# neurite-core.net
KiCad netlist of a schematic drawn in EAGLE
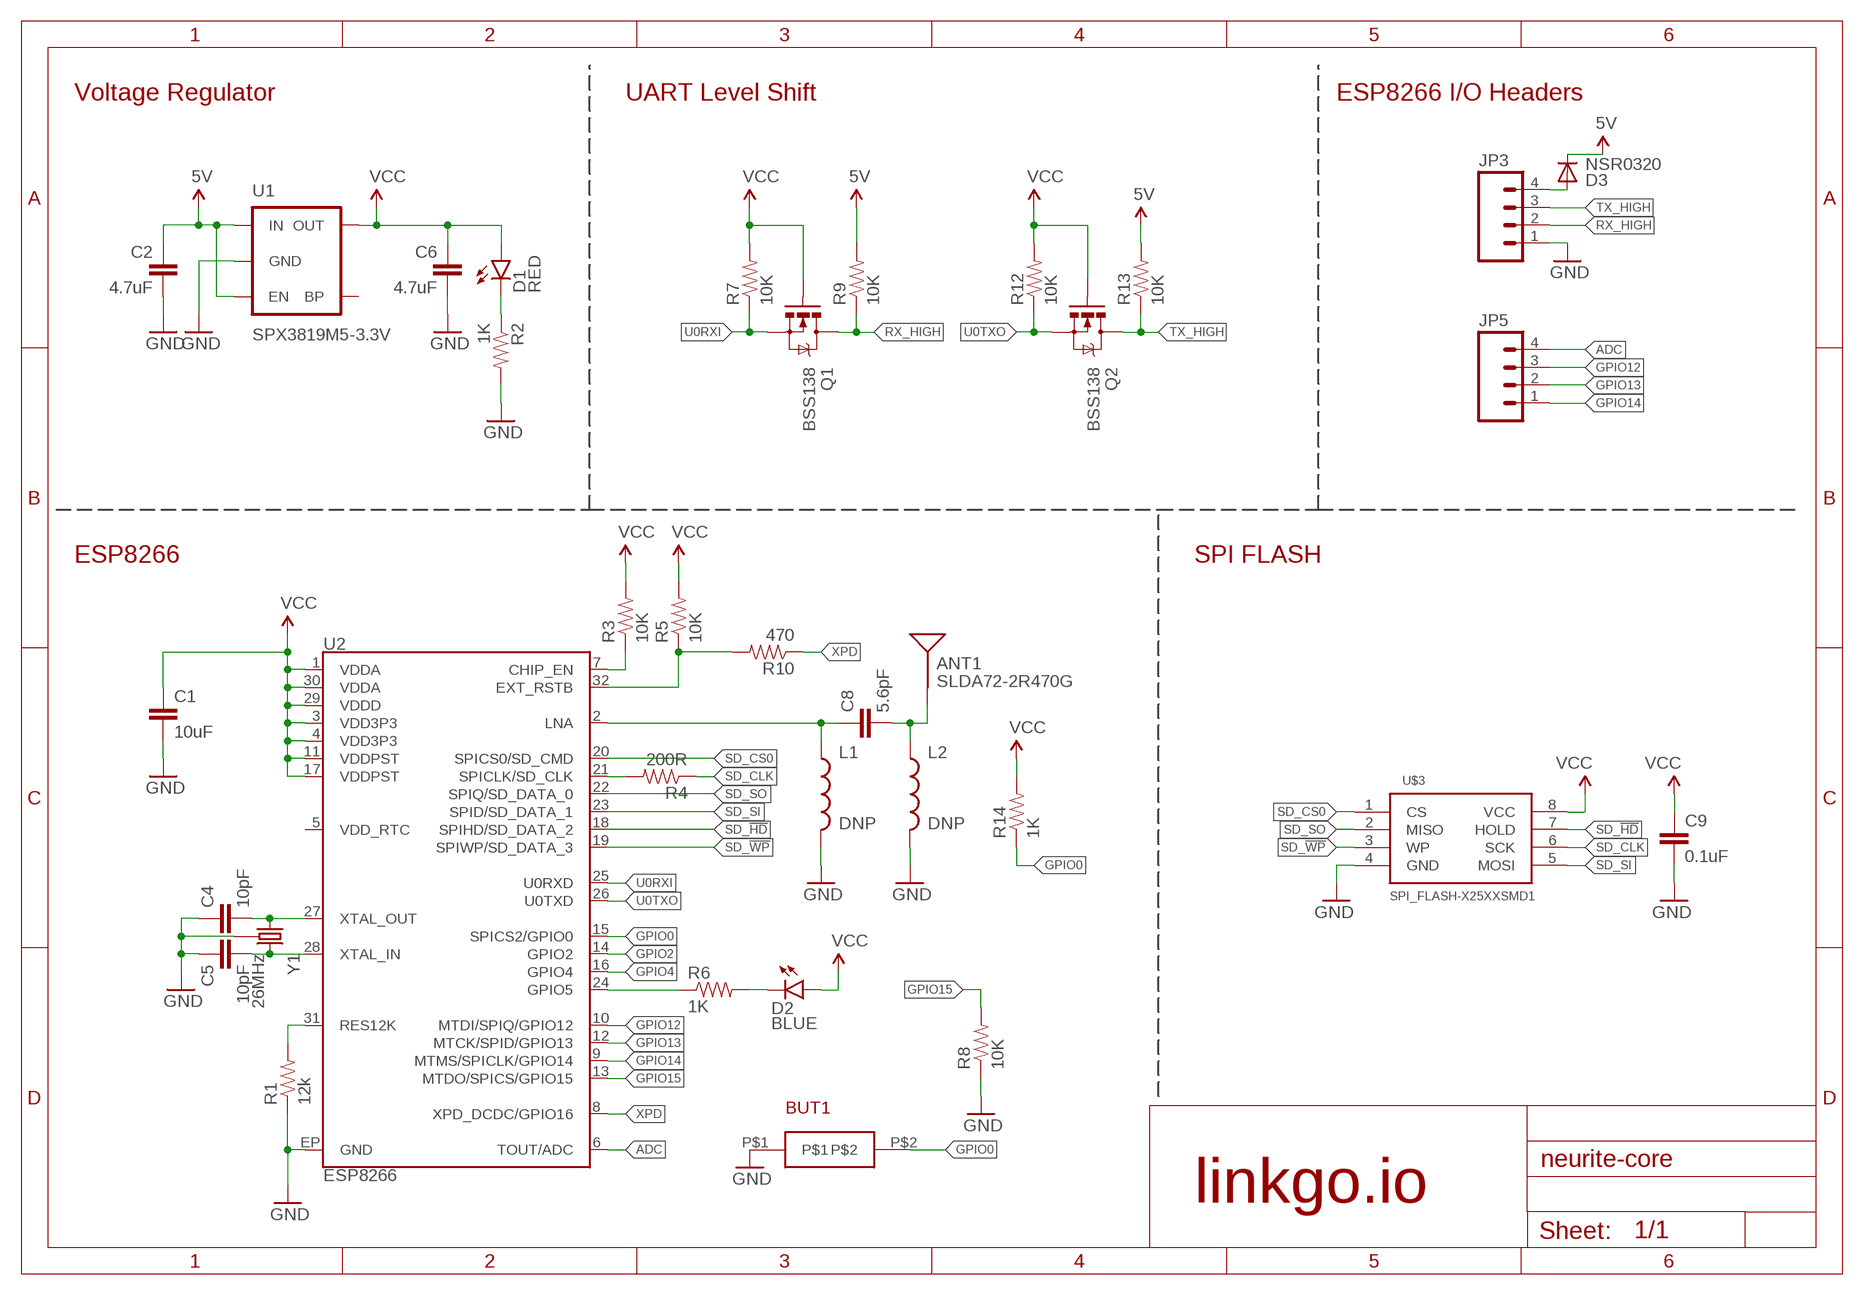
[diagram p0: schematic, sheet 1]

(export (version "E")
  (design (tool "Eeschema 10.0.6"))
  (components
    (comp (ref "ANT1")
      (value "SLDA72-2R470G")
      (footprint "eagle-import:ANTENNA-CHIP6")
      (libsource (lib "eagle-import") (part "ANTENNA2SMD6"))
    )
    (comp (ref "BUT1")
      (value "SWITCH")
      (footprint "eagle-import:SWITCH")
      (libsource (lib "eagle-import") (part "SWITCH"))
    )
    (comp (ref "C1")
      (value "10uF")
      (footprint "eagle-import:0402-CAP")
      (libsource (lib "eagle-import") (part "CAP0402-CAP"))
    )
    (comp (ref "C2")
      (value "4.7uF")
      (footprint "eagle-import:0805")
      (libsource (lib "eagle-import") (part "1.0UF-25V-+80/-20(0805)"))
    )
    (comp (ref "C4")
      (value "10pF")
      (footprint "eagle-import:0402-CAP")
      (libsource (lib "eagle-import") (part "CAP0402-CAP"))
    )
    (comp (ref "C5")
      (value "10pF")
      (footprint "eagle-import:0402-CAP")
      (libsource (lib "eagle-import") (part "CAP0402-CAP"))
    )
    (comp (ref "C6")
      (value "4.7uF")
      (footprint "eagle-import:0603-CAP")
      (libsource (lib "eagle-import") (part "2.2UF-10V-20%(0603)"))
    )
    (comp (ref "C8")
      (value "5.6pF")
      (footprint "eagle-import:0402-CAP")
      (libsource (lib "eagle-import") (part "CAP0402-CAP"))
    )
    (comp (ref "C9")
      (value "0.1uF")
      (footprint "eagle-import:0402-CAP")
      (libsource (lib "eagle-import") (part "CAP0402-CAP"))
    )
    (comp (ref "D1")
      (value "RED")
      (footprint "eagle-import:LED-0603")
      (libsource (lib "eagle-import") (part "LED-RED0603"))
    )
    (comp (ref "D2")
      (value "BLUE")
      (footprint "eagle-import:LED-0603")
      (libsource (lib "eagle-import") (part "LED-BLUE0603"))
    )
    (comp (ref "D3")
      (value "NSR0320")
      (footprint "eagle-import:SOD-323")
      (libsource (lib "eagle-import") (part "DIODESOD"))
    )
    (comp (ref "JP3")
      (value "M04PTH")
      (footprint "eagle-import:1X04")
      (libsource (lib "eagle-import") (part "M04PTH"))
    )
    (comp (ref "JP5")
      (value "M04PTH")
      (footprint "eagle-import:1X04")
      (libsource (lib "eagle-import") (part "M04PTH"))
    )
    (comp (ref "L1")
      (value "DNP")
      (footprint "eagle-import:C0402")
      (libsource (lib "eagle-import") (part "INDUCTOR0402"))
    )
    (comp (ref "L2")
      (value "DNP")
      (footprint "eagle-import:C0402")
      (libsource (lib "eagle-import") (part "INDUCTOR0402"))
    )
    (comp (ref "Q1")
      (value "BSS138")
      (footprint "eagle-import:SOT23-3")
      (libsource (lib "eagle-import") (part "MOSFET-NCHANNELBSS138"))
    )
    (comp (ref "Q2")
      (value "BSS138")
      (footprint "eagle-import:SOT23-3")
      (libsource (lib "eagle-import") (part "MOSFET-NCHANNELBSS138"))
    )
    (comp (ref "R1")
      (value "12k")
      (footprint "eagle-import:0402-RES")
      (libsource (lib "eagle-import") (part "RESISTOR0402-RES"))
    )
    (comp (ref "R2")
      (value "1K")
      (footprint "eagle-import:0402-RES")
      (libsource (lib "eagle-import") (part "RESISTOR0402-RES"))
    )
    (comp (ref "R3")
      (value "10K")
      (footprint "eagle-import:0402-RES")
      (libsource (lib "eagle-import") (part "RESISTOR0402-RES"))
    )
    (comp (ref "R4")
      (value "200R")
      (footprint "eagle-import:0402-RES")
      (libsource (lib "eagle-import") (part "RESISTOR0402-RES"))
    )
    (comp (ref "R5")
      (value "10K")
      (footprint "eagle-import:0402-RES")
      (libsource (lib "eagle-import") (part "RESISTOR0402-RES"))
    )
    (comp (ref "R6")
      (value "1K")
      (footprint "eagle-import:0402-RES")
      (libsource (lib "eagle-import") (part "RESISTOR0402-RES"))
    )
    (comp (ref "R7")
      (value "10K")
      (footprint "eagle-import:0402-RES")
      (libsource (lib "eagle-import") (part "RESISTOR0402-RES"))
    )
    (comp (ref "R8")
      (value "10K")
      (footprint "eagle-import:0402-RES")
      (libsource (lib "eagle-import") (part "RESISTOR0402-RES"))
    )
    (comp (ref "R9")
      (value "10K")
      (footprint "eagle-import:0402-RES")
      (libsource (lib "eagle-import") (part "RESISTOR0402-RES"))
    )
    (comp (ref "R10")
      (value "470")
      (footprint "eagle-import:0402-RES")
      (libsource (lib "eagle-import") (part "RESISTOR0402-RES"))
    )
    (comp (ref "R12")
      (value "10K")
      (footprint "eagle-import:0402-RES")
      (libsource (lib "eagle-import") (part "RESISTOR0402-RES"))
    )
    (comp (ref "R13")
      (value "10K")
      (footprint "eagle-import:0402-RES")
      (libsource (lib "eagle-import") (part "RESISTOR0402-RES"))
    )
    (comp (ref "R14")
      (value "1K")
      (footprint "eagle-import:0402-RES")
      (libsource (lib "eagle-import") (part "RESISTOR0402-RES"))
    )
    (comp (ref "U$3")
      (value "SPI_FLASH-X25XXSMD1")
      (footprint "eagle-import:SO08-EIAJ")
      (libsource (lib "eagle-import") (part "SPI_FLASH-X25XXSMD1"))
    )
    (comp (ref "U1")
      (value "SPX3819M5-3.3V")
      (footprint "eagle-import:SOT23-5")
      (libsource (lib "eagle-import") (part "V_REG_LDOSMD"))
    )
    (comp (ref "U2")
      (value "ESP8266")
      (footprint "eagle-import:QFN32")
      (libsource (lib "eagle-import") (part "ESP8266"))
    )
    (comp (ref "Y1")
      (value "26MHz")
      (footprint "eagle-import:CRYSTAL-SMD-3.2X2.5")
      (libsource (lib "eagle-import") (part "CRYSTAL-GROUNDED3.2X2.5"))
    )
  )
  (nets
    (net (code "1") (name "/SD_~{HD}") (class "Default")
      (node (ref "U$3") (pin "7") (pinfunction "HOLD_7") (pintype "bidirectional"))
      (node (ref "U2") (pin "18") (pinfunction "SPIHD/SD_DATA_2_18") (pintype "bidirectional"))
    )
    (net (code "2") (name "/SD_~{WP}") (class "Default")
      (node (ref "U$3") (pin "3") (pinfunction "WP_3") (pintype "bidirectional"))
      (node (ref "U2") (pin "19") (pinfunction "SPIWP/SD_DATA_3_19") (pintype "bidirectional"))
    )
    (net (code "3") (name "5V") (class "Default")
      (node (ref "C2") (pin "1") (pinfunction "1_1") (pintype "passive"))
      (node (ref "D3") (pin "1") (pinfunction "C_1") (pintype "passive"))
      (node (ref "R13") (pin "2") (pinfunction "2_2") (pintype "passive"))
      (node (ref "R9") (pin "2") (pinfunction "2_2") (pintype "passive"))
      (node (ref "U1") (pin "1") (pinfunction "IN_1") (pintype "input"))
      (node (ref "U1") (pin "3") (pinfunction "EN_3") (pintype "input"))
    )
    (net (code "4") (name "ADC") (class "Default")
      (node (ref "JP5") (pin "4") (pinfunction "4_4") (pintype "passive"))
      (node (ref "U2") (pin "6") (pinfunction "TOUT/ADC_6") (pintype "bidirectional"))
    )
    (net (code "5") (name "GND") (class "Default")
      (node (ref "BUT1") (pin "P$1") (pinfunction "P$1_P$1") (pintype "bidirectional"))
      (node (ref "C1") (pin "2") (pinfunction "2_2") (pintype "passive"))
      (node (ref "C2") (pin "2") (pinfunction "2_2") (pintype "passive"))
      (node (ref "C4") (pin "1") (pinfunction "1_1") (pintype "passive"))
      (node (ref "C5") (pin "1") (pinfunction "1_1") (pintype "passive"))
      (node (ref "C6") (pin "2") (pinfunction "2_2") (pintype "passive"))
      (node (ref "C9") (pin "2") (pinfunction "2_2") (pintype "passive"))
      (node (ref "JP3") (pin "1") (pinfunction "1_1") (pintype "passive"))
      (node (ref "L1") (pin "2") (pinfunction "2_2") (pintype "passive"))
      (node (ref "L2") (pin "2") (pinfunction "2_2") (pintype "passive"))
      (node (ref "R1") (pin "1") (pinfunction "1_1") (pintype "passive"))
      (node (ref "R2") (pin "2") (pinfunction "2_2") (pintype "passive"))
      (node (ref "R8") (pin "1") (pinfunction "1_1") (pintype "passive"))
      (node (ref "U$3") (pin "4") (pinfunction "GND_4") (pintype "bidirectional"))
      (node (ref "U1") (pin "2") (pinfunction "GND_2") (pintype "input"))
      (node (ref "U2") (pin "EP") (pinfunction "GND_EP") (pintype "bidirectional"))
      (node (ref "Y1") (pin "2") (pinfunction "GND_2") (pintype "passive"))
      (node (ref "Y1") (pin "4") (pinfunction "GND_4") (pintype "passive"))
    )
    (net (code "6") (name "GPIO0") (class "Default")
      (node (ref "BUT1") (pin "P$2") (pinfunction "P$2_P$2") (pintype "bidirectional"))
      (node (ref "R14") (pin "1") (pinfunction "1_1") (pintype "passive"))
      (node (ref "U2") (pin "15") (pinfunction "SPICS2/GPIO0_15") (pintype "bidirectional"))
    )
    (net (code "7") (name "GPIO2") (class "Default")
      (node (ref "U2") (pin "14") (pinfunction "GPIO2_14") (pintype "bidirectional"))
    )
    (net (code "8") (name "GPIO4") (class "Default")
      (node (ref "U2") (pin "16") (pinfunction "GPIO4_16") (pintype "bidirectional"))
    )
    (net (code "9") (name "GPIO12") (class "Default")
      (node (ref "JP5") (pin "3") (pinfunction "3_3") (pintype "passive"))
      (node (ref "U2") (pin "10") (pinfunction "MTDI/SPIQ/GPIO12_10") (pintype "bidirectional"))
    )
    (net (code "10") (name "GPIO13") (class "Default")
      (node (ref "JP5") (pin "2") (pinfunction "2_2") (pintype "passive"))
      (node (ref "U2") (pin "12") (pinfunction "MTCK/SPID/GPIO13_12") (pintype "bidirectional"))
    )
    (net (code "11") (name "GPIO14") (class "Default")
      (node (ref "JP5") (pin "1") (pinfunction "1_1") (pintype "passive"))
      (node (ref "U2") (pin "9") (pinfunction "MTMS/SPICLK/GPIO14_9") (pintype "bidirectional"))
    )
    (net (code "12") (name "GPIO15") (class "Default")
      (node (ref "R8") (pin "2") (pinfunction "2_2") (pintype "passive"))
      (node (ref "U2") (pin "13") (pinfunction "MTDO/SPICS/GPIO15_13") (pintype "bidirectional"))
    )
    (net (code "13") (name "Net-(ANT1-SIGNAL)") (class "Default")
      (node (ref "ANT1") (pin "1") (pinfunction "SIGNAL_1") (pintype "bidirectional"))
      (node (ref "C8") (pin "2") (pinfunction "2_2") (pintype "passive"))
      (node (ref "L2") (pin "1") (pinfunction "1_1") (pintype "passive"))
    )
    (net (code "14") (name "Net-(D1-PadC)") (class "Default")
      (node (ref "D1") (pin "C") (pinfunction "C_C") (pintype "passive"))
      (node (ref "R2") (pin "1") (pinfunction "1_1") (pintype "passive"))
    )
    (net (code "15") (name "Net-(D2-PadC)") (class "Default")
      (node (ref "D2") (pin "C") (pinfunction "C_C") (pintype "passive"))
      (node (ref "R6") (pin "2") (pinfunction "2_2") (pintype "passive"))
    )
    (net (code "16") (name "Net-(D3-A)") (class "Default")
      (node (ref "D3") (pin "2") (pinfunction "A_2") (pintype "passive"))
      (node (ref "JP3") (pin "4") (pinfunction "4_4") (pintype "passive"))
    )
    (net (code "17") (name "Net-(U2-CHIP_EN)") (class "Default")
      (node (ref "R3") (pin "1") (pinfunction "1_1") (pintype "passive"))
      (node (ref "U2") (pin "7") (pinfunction "CHIP_EN_7") (pintype "bidirectional"))
    )
    (net (code "18") (name "Net-(U2-EXT_RSTB)") (class "Default")
      (node (ref "R10") (pin "2") (pinfunction "2_2") (pintype "passive"))
      (node (ref "R5") (pin "1") (pinfunction "1_1") (pintype "passive"))
      (node (ref "U2") (pin "32") (pinfunction "EXT_RSTB_32") (pintype "bidirectional"))
    )
    (net (code "19") (name "Net-(U2-GPIO5)") (class "Default")
      (node (ref "R6") (pin "1") (pinfunction "1_1") (pintype "passive"))
      (node (ref "U2") (pin "24") (pinfunction "GPIO5_24") (pintype "bidirectional"))
    )
    (net (code "20") (name "Net-(U2-LNA)") (class "Default")
      (node (ref "C8") (pin "1") (pinfunction "1_1") (pintype "passive"))
      (node (ref "L1") (pin "1") (pinfunction "1_1") (pintype "passive"))
      (node (ref "U2") (pin "2") (pinfunction "LNA_2") (pintype "bidirectional"))
    )
    (net (code "21") (name "Net-(U2-RES12K)") (class "Default")
      (node (ref "R1") (pin "2") (pinfunction "2_2") (pintype "passive"))
      (node (ref "U2") (pin "31") (pinfunction "RES12K_31") (pintype "bidirectional"))
    )
    (net (code "22") (name "Net-(U2-SPICLK{slash}SD_CLK)") (class "Default")
      (node (ref "R4") (pin "2") (pinfunction "2_2") (pintype "passive"))
      (node (ref "U2") (pin "21") (pinfunction "SPICLK/SD_CLK_21") (pintype "bidirectional"))
    )
    (net (code "23") (name "Net-(U2-XTAL_IN)") (class "Default")
      (node (ref "C5") (pin "2") (pinfunction "2_2") (pintype "passive"))
      (node (ref "U2") (pin "28") (pinfunction "XTAL_IN_28") (pintype "bidirectional"))
      (node (ref "Y1") (pin "3") (pinfunction "2_3") (pintype "passive"))
    )
    (net (code "24") (name "Net-(U2-XTAL_OUT)") (class "Default")
      (node (ref "C4") (pin "2") (pinfunction "2_2") (pintype "passive"))
      (node (ref "U2") (pin "27") (pinfunction "XTAL_OUT_27") (pintype "bidirectional"))
      (node (ref "Y1") (pin "1") (pinfunction "1_1") (pintype "passive"))
    )
    (net (code "25") (name "RX_HIGH") (class "Default")
      (node (ref "JP3") (pin "2") (pinfunction "2_2") (pintype "passive"))
      (node (ref "Q1") (pin "3") (pinfunction "D_3") (pintype "passive"))
      (node (ref "R9") (pin "1") (pinfunction "1_1") (pintype "passive"))
    )
    (net (code "26") (name "SD_CLK") (class "Default")
      (node (ref "R4") (pin "1") (pinfunction "1_1") (pintype "passive"))
      (node (ref "U$3") (pin "6") (pinfunction "SCK_6") (pintype "bidirectional"))
    )
    (net (code "27") (name "SD_CS0") (class "Default")
      (node (ref "U$3") (pin "1") (pinfunction "CS_1") (pintype "bidirectional"))
      (node (ref "U2") (pin "20") (pinfunction "SPICS0/SD_CMD_20") (pintype "bidirectional"))
    )
    (net (code "28") (name "SD_SI") (class "Default")
      (node (ref "U$3") (pin "5") (pinfunction "MOSI_5") (pintype "bidirectional"))
      (node (ref "U2") (pin "23") (pinfunction "SPID/SD_DATA_1_23") (pintype "bidirectional"))
    )
    (net (code "29") (name "SD_SO") (class "Default")
      (node (ref "U$3") (pin "2") (pinfunction "MISO_2") (pintype "bidirectional"))
      (node (ref "U2") (pin "22") (pinfunction "SPIQ/SD_DATA_0_22") (pintype "bidirectional"))
    )
    (net (code "30") (name "TX_HIGH") (class "Default")
      (node (ref "JP3") (pin "3") (pinfunction "3_3") (pintype "passive"))
      (node (ref "Q2") (pin "3") (pinfunction "D_3") (pintype "passive"))
      (node (ref "R13") (pin "1") (pinfunction "1_1") (pintype "passive"))
    )
    (net (code "31") (name "U0RXI") (class "Default")
      (node (ref "Q1") (pin "2") (pinfunction "S_2") (pintype "passive"))
      (node (ref "R7") (pin "1") (pinfunction "1_1") (pintype "passive"))
      (node (ref "U2") (pin "25") (pinfunction "U0RXD_25") (pintype "bidirectional"))
    )
    (net (code "32") (name "U0TXO") (class "Default")
      (node (ref "Q2") (pin "2") (pinfunction "S_2") (pintype "passive"))
      (node (ref "R12") (pin "1") (pinfunction "1_1") (pintype "passive"))
      (node (ref "U2") (pin "26") (pinfunction "U0TXD_26") (pintype "bidirectional"))
    )
    (net (code "33") (name "VCC") (class "Default")
      (node (ref "C1") (pin "1") (pinfunction "1_1") (pintype "passive"))
      (node (ref "C6") (pin "1") (pinfunction "1_1") (pintype "passive"))
      (node (ref "C9") (pin "1") (pinfunction "1_1") (pintype "passive"))
      (node (ref "D1") (pin "A") (pinfunction "A_A") (pintype "passive"))
      (node (ref "D2") (pin "A") (pinfunction "A_A") (pintype "passive"))
      (node (ref "Q1") (pin "1") (pinfunction "G_1") (pintype "passive"))
      (node (ref "Q2") (pin "1") (pinfunction "G_1") (pintype "passive"))
      (node (ref "R12") (pin "2") (pinfunction "2_2") (pintype "passive"))
      (node (ref "R14") (pin "2") (pinfunction "2_2") (pintype "passive"))
      (node (ref "R3") (pin "2") (pinfunction "2_2") (pintype "passive"))
      (node (ref "R5") (pin "2") (pinfunction "2_2") (pintype "passive"))
      (node (ref "R7") (pin "2") (pinfunction "2_2") (pintype "passive"))
      (node (ref "U$3") (pin "8") (pinfunction "VCC_8") (pintype "bidirectional"))
      (node (ref "U1") (pin "5") (pinfunction "OUT_5") (pintype "passive"))
      (node (ref "U2") (pin "1") (pinfunction "VDDA_1") (pintype "bidirectional"))
      (node (ref "U2") (pin "11") (pinfunction "VDDPST_11") (pintype "bidirectional"))
      (node (ref "U2") (pin "17") (pinfunction "VDDPST_17") (pintype "bidirectional"))
      (node (ref "U2") (pin "29") (pinfunction "VDDD_29") (pintype "bidirectional"))
      (node (ref "U2") (pin "3") (pinfunction "VDD3P3_3") (pintype "bidirectional"))
      (node (ref "U2") (pin "30") (pinfunction "VDDA_30") (pintype "bidirectional"))
      (node (ref "U2") (pin "4") (pinfunction "VDD3P3_4") (pintype "bidirectional"))
    )
    (net (code "34") (name "XPD") (class "Default")
      (node (ref "R10") (pin "1") (pinfunction "1_1") (pintype "passive"))
      (node (ref "U2") (pin "8") (pinfunction "XPD_DCDC/GPIO16_8") (pintype "bidirectional"))
    )
    (net (code "35") (name "unconnected-(U1-BP-Pad4)") (class "Default")
      (node (ref "U1") (pin "4") (pinfunction "BP_4") (pintype "input"))
    )
    (net (code "36") (name "unconnected-(U2-VDD_RTC-Pad5)") (class "Default")
      (node (ref "U2") (pin "5") (pinfunction "VDD_RTC_5") (pintype "bidirectional"))
    )
  )
)
